# motion.net
KiCad netlist of a schematic drawn in Altium Designer
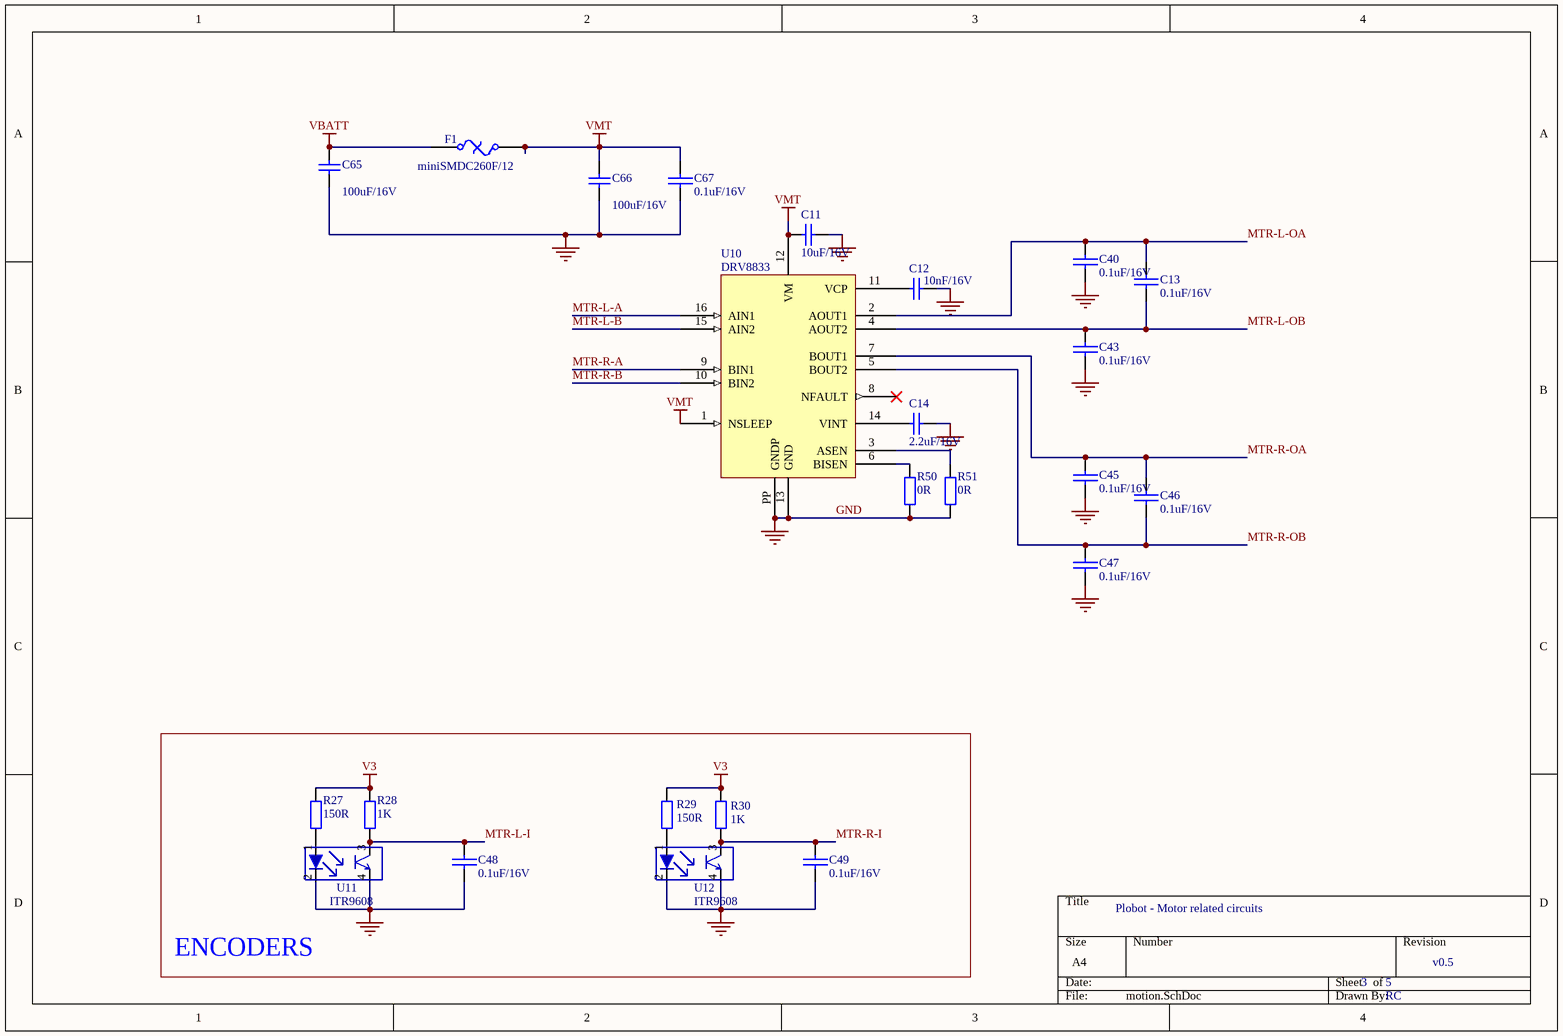
[diagram p0: motion.SchDoc]

(export (version "E")
  (design (tool "Eeschema 10.0.6"))
  (components
    (comp (ref "C11")
      (value "10uF/16V")
      (footprint "CAPC1608N")
      (description "Capacitor")
      (fields (field (name "PUBLISHER") "Altium Limited"))
      (libsource (lib "main_pcb") (part "Cap_2"))
    )
    (comp (ref "C12")
      (value "10nF/16V")
      (footprint "CAPC1608N")
      (description "Capacitor")
      (fields (field (name "PUBLISHER") "Altium Limited"))
      (libsource (lib "") (part "Cap_1"))
    )
    (comp (ref "C13")
      (value "0.1uF/16V")
      (footprint "CAPC1608N")
      (description "Capacitor")
      (libsource (lib "*") (part "Cap"))
    )
    (comp (ref "C14")
      (value "2.2uF/16V")
      (footprint "CAPC1608N")
      (description "Capacitor")
      (fields (field (name "PUBLISHER") "Altium Limited"))
      (libsource (lib "") (part "Cap_1"))
    )
    (comp (ref "C40")
      (value "0.1uF/16V")
      (footprint "CAPC1608N")
      (description "Capacitor")
      (libsource (lib "*") (part "Cap"))
    )
    (comp (ref "C43")
      (value "0.1uF/16V")
      (footprint "CAPC1608N")
      (description "Capacitor")
      (libsource (lib "*") (part "Cap"))
    )
    (comp (ref "C45")
      (value "0.1uF/16V")
      (footprint "CAPC1608N")
      (description "Capacitor")
      (libsource (lib "*") (part "Cap"))
    )
    (comp (ref "C46")
      (value "0.1uF/16V")
      (footprint "CAPC1608N")
      (description "Capacitor")
      (libsource (lib "*") (part "Cap"))
    )
    (comp (ref "C47")
      (value "0.1uF/16V")
      (footprint "CAPC1608N")
      (description "Capacitor")
      (libsource (lib "*") (part "Cap"))
    )
    (comp (ref "C48")
      (value "0.1uF/16V")
      (footprint "CAPC1608N")
      (description "Capacitor")
      (libsource (lib "*") (part "Cap"))
    )
    (comp (ref "C49")
      (value "0.1uF/16V")
      (footprint "plobot_review:CAPC1608N")
      (description "Capacitor")
      (libsource (lib "*") (part "Cap"))
    )
    (comp (ref "C65")
      (value "100uF/16V")
      (footprint "Cap6.6X6.6")
      (description "Capacitor")
      (fields (field (name "PUBLISHER") "Altium Limited"))
      (libsource (lib "Miscellaneous Devices") (part "Cap"))
    )
    (comp (ref "C66")
      (value "100uF/16V")
      (footprint "Cap6.6X6.6")
      (description "Capacitor")
      (fields (field (name "PUBLISHER") "Altium Limited"))
      (libsource (lib "Miscellaneous Devices") (part "Cap"))
    )
    (comp (ref "C67")
      (value "0.1uF/16V")
      (footprint "CAPC1608N")
      (description "Capacitor")
      (libsource (lib "*") (part "Cap"))
    )
    (comp (ref "F1")
      (value "miniSMDC260F/12")
      (footprint "miniSMDC260F/12")
      (description "Thermal Fuse")
      (fields (field (name "PUBLISHER") "Altium Limited"))
      (libsource (lib "Miscellaneous Devices") (part "Fuse Thermal"))
    )
    (comp (ref "R27")
      (value "150R")
      (footprint "plobot_review:RESC1608N")
      (description "Resistor")
      (fields (field (name "PUBLISHER") "Altium Limited"))
      (libsource (lib "*") (part "Res2"))
    )
    (comp (ref "R28")
      (value "1K")
      (footprint "plobot_review:RESC1608N")
      (description "Resistor")
      (fields (field (name "PUBLISHER") "Altium Limited"))
      (libsource (lib "*") (part "Res2"))
    )
    (comp (ref "R29")
      (value "150R")
      (footprint "plobot_review:RESC1608N")
      (description "Resistor")
      (fields (field (name "PUBLISHER") "Altium Limited"))
      (libsource (lib "*") (part "Res2"))
    )
    (comp (ref "R30")
      (value "1K")
      (footprint "plobot_review:RESC1608N")
      (description "Resistor")
      (fields (field (name "PUBLISHER") "Altium Limited"))
      (libsource (lib "*") (part "Res2"))
    )
    (comp (ref "R50")
      (value "0R")
      (footprint "RESC1608N")
      (description "Resistor")
      (fields (field (name "PUBLISHER") "Altium Limited"))
      (libsource (lib "*") (part "Res2"))
    )
    (comp (ref "R51")
      (value "0R")
      (footprint "RESC1608N")
      (description "Resistor")
      (fields (field (name "PUBLISHER") "Altium Limited"))
      (libsource (lib "*") (part "Res2"))
    )
    (comp (ref "U10") (value "DRV8833") (footprint "DRV8833") (libsource (lib "components") (part "DRV8833")))
    (comp (ref "U11")
      (value "ITR9608")
      (footprint "plobot_review:ITR9608")
      (libsource (lib "*") (part "ITR9608"))
    )
    (comp (ref "U12")
      (value "ITR9608")
      (footprint "plobot_review:ITR9608")
      (libsource (lib "*") (part "ITR9608"))
    )
  )
  (nets
    (net (code "1") (name "/MTR-L-A") (class "Default")
      (node (ref "U10") (pin "16") (pinfunction "AIN1_16") (pintype "input"))
    )
    (net (code "2") (name "/MTR-L-B") (class "Default")
      (node (ref "U10") (pin "15") (pinfunction "AIN2_15") (pintype "input"))
    )
    (net (code "3") (name "/MTR-L-I") (class "Default")
      (node (ref "C48") (pin "2") (pinfunction "2_2") (pintype "passive"))
      (node (ref "R28") (pin "1") (pinfunction "1_1") (pintype "passive"))
      (node (ref "U11") (pin "3") (pinfunction "COLLECTOR_3") (pintype "passive"))
    )
    (net (code "4") (name "/MTR-L-OA") (class "Default")
      (node (ref "C13") (pin "2") (pinfunction "2_2") (pintype "passive"))
      (node (ref "C40") (pin "2") (pinfunction "2_2") (pintype "passive"))
      (node (ref "U10") (pin "2") (pinfunction "AOUT1_2") (pintype "power_in"))
    )
    (net (code "5") (name "/MTR-L-OB") (class "Default")
      (node (ref "C13") (pin "1") (pinfunction "1_1") (pintype "passive"))
      (node (ref "C43") (pin "2") (pinfunction "2_2") (pintype "passive"))
      (node (ref "U10") (pin "4") (pinfunction "AOUT2_4") (pintype "power_in"))
    )
    (net (code "6") (name "/MTR-R-A") (class "Default")
      (node (ref "U10") (pin "9") (pinfunction "BIN1_9") (pintype "input"))
    )
    (net (code "7") (name "/MTR-R-B") (class "Default")
      (node (ref "U10") (pin "10") (pinfunction "BIN2_10") (pintype "input"))
    )
    (net (code "8") (name "/MTR-R-I") (class "Default")
      (node (ref "C49") (pin "2") (pinfunction "2_2") (pintype "passive"))
      (node (ref "R30") (pin "1") (pinfunction "1_1") (pintype "passive"))
      (node (ref "U12") (pin "3") (pinfunction "COLLECTOR_3") (pintype "passive"))
    )
    (net (code "9") (name "/MTR-R-OA") (class "Default")
      (node (ref "C45") (pin "2") (pinfunction "2_2") (pintype "passive"))
      (node (ref "C46") (pin "2") (pinfunction "2_2") (pintype "passive"))
      (node (ref "U10") (pin "7") (pinfunction "BOUT1_7") (pintype "power_in"))
    )
    (net (code "10") (name "/MTR-R-OB") (class "Default")
      (node (ref "C46") (pin "1") (pinfunction "1_1") (pintype "passive"))
      (node (ref "C47") (pin "2") (pinfunction "2_2") (pintype "passive"))
      (node (ref "U10") (pin "5") (pinfunction "BOUT2_5") (pintype "power_in"))
    )
    (net (code "11") (name "GND") (class "Default")
      (node (ref "C11") (pin "1") (pinfunction "1_1") (pintype "passive"))
      (node (ref "C12") (pin "1") (pinfunction "1_1") (pintype "passive"))
      (node (ref "C14") (pin "1") (pinfunction "1_1") (pintype "passive"))
      (node (ref "C40") (pin "1") (pinfunction "1_1") (pintype "passive"))
      (node (ref "C43") (pin "1") (pinfunction "1_1") (pintype "passive"))
      (node (ref "C45") (pin "1") (pinfunction "1_1") (pintype "passive"))
      (node (ref "C47") (pin "1") (pinfunction "1_1") (pintype "passive"))
      (node (ref "C48") (pin "1") (pinfunction "1_1") (pintype "passive"))
      (node (ref "C49") (pin "1") (pinfunction "1_1") (pintype "passive"))
      (node (ref "C65") (pin "1") (pinfunction "1_1") (pintype "passive"))
      (node (ref "C66") (pin "1") (pinfunction "1_1") (pintype "passive"))
      (node (ref "C67") (pin "1") (pinfunction "1_1") (pintype "passive"))
      (node (ref "R50") (pin "1") (pinfunction "1_1") (pintype "passive"))
      (node (ref "R51") (pin "1") (pinfunction "1_1") (pintype "passive"))
      (node (ref "U10") (pin "13") (pinfunction "GND_13") (pintype "power_in"))
      (node (ref "U10") (pin "PP") (pinfunction "GNDP_PP") (pintype "power_in"))
      (node (ref "U11") (pin "2") (pinfunction "CATHODE_2") (pintype "passive"))
      (node (ref "U11") (pin "4") (pinfunction "ENITIER_4") (pintype "passive"))
      (node (ref "U12") (pin "2") (pinfunction "CATHODE_2") (pintype "passive"))
      (node (ref "U12") (pin "4") (pinfunction "ENITIER_4") (pintype "passive"))
    )
    (net (code "12") (name "Net-(U10-ASEN)") (class "Default")
      (node (ref "R51") (pin "2") (pinfunction "2_2") (pintype "passive"))
      (node (ref "U10") (pin "3") (pinfunction "ASEN_3") (pintype "power_in"))
    )
    (net (code "13") (name "Net-(U10-BISEN)") (class "Default")
      (node (ref "R50") (pin "2") (pinfunction "2_2") (pintype "passive"))
      (node (ref "U10") (pin "6") (pinfunction "BISEN_6") (pintype "power_in"))
    )
    (net (code "14") (name "Net-(U10-VCP)") (class "Default")
      (node (ref "C12") (pin "2") (pinfunction "2_2") (pintype "passive"))
      (node (ref "U10") (pin "11") (pinfunction "VCP_11") (pintype "power_in"))
    )
    (net (code "15") (name "Net-(U10-VINT)") (class "Default")
      (node (ref "C14") (pin "2") (pinfunction "2_2") (pintype "passive"))
      (node (ref "U10") (pin "14") (pinfunction "VINT_14") (pintype "power_in"))
    )
    (net (code "16") (name "Net-(U11-ANODE)") (class "Default")
      (node (ref "R27") (pin "1") (pinfunction "1_1") (pintype "passive"))
      (node (ref "U11") (pin "1") (pinfunction "ANODE_1") (pintype "passive"))
    )
    (net (code "17") (name "Net-(U12-ANODE)") (class "Default")
      (node (ref "R29") (pin "1") (pinfunction "1_1") (pintype "passive"))
      (node (ref "U12") (pin "1") (pinfunction "ANODE_1") (pintype "passive"))
    )
    (net (code "18") (name "V3") (class "Default")
      (node (ref "R27") (pin "2") (pinfunction "2_2") (pintype "passive"))
      (node (ref "R28") (pin "2") (pinfunction "2_2") (pintype "passive"))
      (node (ref "R29") (pin "2") (pinfunction "2_2") (pintype "passive"))
      (node (ref "R30") (pin "2") (pinfunction "2_2") (pintype "passive"))
    )
    (net (code "19") (name "VBATT") (class "Default")
      (node (ref "C65") (pin "2") (pinfunction "2_2") (pintype "passive"))
      (node (ref "F1") (pin "1") (pinfunction "1_1") (pintype "passive"))
    )
    (net (code "20") (name "VMT") (class "Default")
      (node (ref "C11") (pin "2") (pinfunction "2_2") (pintype "passive"))
      (node (ref "C66") (pin "2") (pinfunction "2_2") (pintype "passive"))
      (node (ref "C67") (pin "2") (pinfunction "2_2") (pintype "passive"))
      (node (ref "F1") (pin "2") (pinfunction "2_2") (pintype "passive"))
      (node (ref "U10") (pin "1") (pinfunction "NSLEEP_1") (pintype "input"))
      (node (ref "U10") (pin "12") (pinfunction "VM_12") (pintype "power_in"))
    )
    (net (code "21") (name "unconnected-(U10-NFAULT-Pad8)") (class "Default")
      (node (ref "U10") (pin "8") (pinfunction "NFAULT_8") (pintype "output+no_connect"))
    )
  )
)
